# TEC_power1.net
KiCad netlist of a schematic drawn in Altium Designer
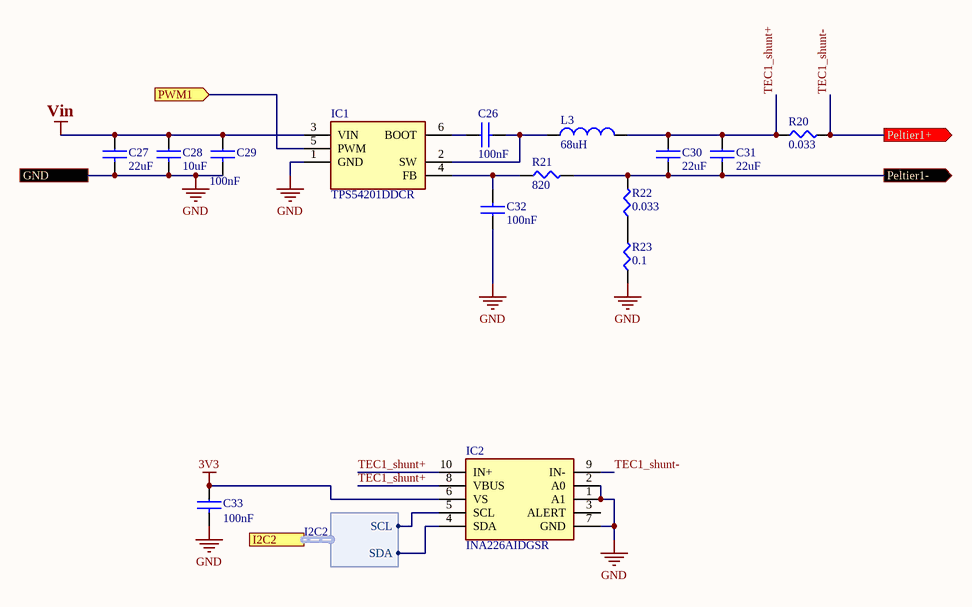
[diagram p0: TEC power1.SchDoc]

(export (version "E")
  (design (tool "Eeschema 10.0.6"))
  (components
    (comp (ref "C26")
      (value "100nF")
      (footprint "CAPC160X80X90L35N")
      (fields (field (name "LCSC PART #") "C14663") (field (name "PART NUMBER") "CC0603KRX7R9BB104"))
      (libsource (lib "Miscellaneous") (part "capacitor"))
    )
    (comp (ref "C27")
      (value "22uF")
      (footprint "CAPC200X125X110L50N")
      (fields (field (name "LCSC PART #") "C45783") (field (name "PART NUMBER") "CL21A226MAQNNNE"))
      (libsource (lib "Miscellaneous") (part "capacitor"))
    )
    (comp (ref "C28")
      (value "10uF")
      (footprint "CAPC200X125X110L50N")
      (fields (field (name "LCSC PART #") "C15850") (field (name "PART NUMBER") "CL21A106KAYNNNE"))
      (libsource (lib "Miscellaneous") (part "capacitor"))
    )
    (comp (ref "C29")
      (value "100nF")
      (footprint "CAPC160X80X90L35N")
      (fields (field (name "LCSC PART #") "C14663") (field (name "PART NUMBER") "CC0603KRX7R9BB104"))
      (libsource (lib "Miscellaneous") (part "capacitor"))
    )
    (comp (ref "C30")
      (value "22uF")
      (footprint "CAPC200X125X110L50N")
      (fields (field (name "LCSC PART #") "C45783") (field (name "PART NUMBER") "CL21A226MAQNNNE"))
      (libsource (lib "Miscellaneous") (part "capacitor"))
    )
    (comp (ref "C31")
      (value "22uF")
      (footprint "CAPC200X125X110L50N")
      (fields (field (name "LCSC PART #") "C45783") (field (name "PART NUMBER") "CL21A226MAQNNNE"))
      (libsource (lib "Miscellaneous") (part "capacitor"))
    )
    (comp (ref "C32")
      (value "100nF")
      (footprint "CAPC160X80X90L35N")
      (fields (field (name "LCSC PART #") "C14663") (field (name "PART NUMBER") "CC0603KRX7R9BB104"))
      (libsource (lib "Miscellaneous") (part "capacitor"))
    )
    (comp (ref "C33")
      (value "100nF")
      (footprint "CAPC160X80X90L35N")
      (fields (field (name "LCSC PART #") "C14663") (field (name "PART NUMBER") "CC0603KRX7R9BB104"))
      (libsource (lib "Miscellaneous") (part "capacitor"))
    )
    (comp (ref "IC1")
      (value "TPS54201DDCR")
      (footprint "SOT95P280X110-6N")
      (description "Integrated Circuit")
      (fields (field (name "MOUSER2 PART NUMBER") "595-TPS54201DDCR") (field (name "PART NUMBER") "TPS54201"))
      (libsource (lib "Miscellaneous") (part "TPS54201DDCR_1"))
    )
    (comp (ref "IC2")
      (value "INA226AIDGSR")
      (footprint "SOP10P50_300X490X110L55X22N")
      (description "Integrated Circuit")
      (fields (field (name "MOUSER2 PART NUMBER") "595-INA226AIDGSR") (field (name "LCSC PART #") "C49851"))
      (libsource (lib "Miscellaneous") (part "INA226AIDGSR"))
    )
    (comp (ref "L3")
      (value "68uH")
      (footprint "INDM1250X1250X800L290X540N")
      (description "Inductor")
      (fields (field (name "LCSC PART #") "C169377") (field (name "PART NUMBER") "SWRB1207S-680MT"))
      (libsource (lib "Miscellaneous") (part "Inductor"))
    )
    (comp (ref "R20")
      (value "0.033")
      (footprint "RESC200X125X70L40N")
      (fields (field (name "LCSC PART #") "C127689"))
      (libsource (lib "Miscellaneous") (part "Resistor"))
    )
    (comp (ref "R21")
      (value "820")
      (footprint "RESC160X80X90L30N")
      (fields (field (name "PART NUMBER") "0603WAF8200T5E") (field (name "LCSC PART #") "C23253"))
      (libsource (lib "Miscellaneous") (part "Resistor"))
    )
    (comp (ref "R22")
      (value "0.033")
      (footprint "RESC200X125X70L40N")
      (fields (field (name "PART NUMBER") "0805W8F330MT5E") (field (name "LCSC PART #") "C127689"))
      (libsource (lib "Miscellaneous") (part "Resistor"))
    )
    (comp (ref "R23")
      (value "0.1")
      (footprint "RESC310X152X65L45N")
      (fields (field (name "PART NUMBER") "1206W4F100LT5E") (field (name "LCSC PART #") "C25334"))
      (libsource (lib "Miscellaneous") (part "Resistor"))
    )
  )
  (nets
    (net (code "2") (name "/PWM1") (class "Default")
      (node (ref "IC1") (pin "5") (pinfunction "PWM_5") (pintype "passive"))
    )
    (net (code "3") (name "/Peltier1-") (class "Default")
      (node (ref "C30") (pin "2") (pinfunction "2_2") (pintype "passive"))
      (node (ref "C31") (pin "2") (pinfunction "2_2") (pintype "passive"))
      (node (ref "R21") (pin "2") (pinfunction "2_2") (pintype "passive"))
      (node (ref "R22") (pin "2") (pinfunction "2_2") (pintype "passive"))
    )
    (net (code "4") (name "/SCL") (class "Default")
      (node (ref "IC2") (pin "5") (pinfunction "SCL_5") (pintype "passive"))
    )
    (net (code "5") (name "/SDA") (class "Default")
      (node (ref "IC2") (pin "4") (pinfunction "SDA_4") (pintype "passive"))
    )
    (net (code "6") (name "/TEC1_shunt+") (class "Default")
      (node (ref "C30") (pin "1") (pinfunction "1_1") (pintype "passive"))
      (node (ref "C31") (pin "1") (pinfunction "1_1") (pintype "passive"))
      (node (ref "IC2") (pin "10") (pinfunction "IN+_10") (pintype "passive"))
      (node (ref "IC2") (pin "8") (pinfunction "VBUS_8") (pintype "passive"))
      (node (ref "L3") (pin "2") (pinfunction "2_2") (pintype "passive"))
      (node (ref "R20") (pin "1") (pinfunction "1_1") (pintype "passive"))
    )
    (net (code "7") (name "/TEC1_shunt-") (class "Default")
      (node (ref "IC2") (pin "9") (pinfunction "IN-_9") (pintype "passive"))
      (node (ref "R20") (pin "2") (pinfunction "2_2") (pintype "passive"))
    )
    (net (code "9") (name "3V3") (class "Default")
      (node (ref "C33") (pin "1") (pinfunction "1_1") (pintype "passive"))
      (node (ref "IC2") (pin "6") (pinfunction "VS_6") (pintype "passive"))
    )
    (net (code "10") (name "GND") (class "Default")
      (node (ref "C27") (pin "2") (pinfunction "2_2") (pintype "passive"))
      (node (ref "C28") (pin "2") (pinfunction "2_2") (pintype "passive"))
      (node (ref "C29") (pin "2") (pinfunction "2_2") (pintype "passive"))
      (node (ref "C32") (pin "1") (pinfunction "1_1") (pintype "passive"))
      (node (ref "C33") (pin "2") (pinfunction "2_2") (pintype "passive"))
      (node (ref "IC1") (pin "1") (pinfunction "GND_1") (pintype "passive"))
      (node (ref "IC2") (pin "1") (pinfunction "A1_1") (pintype "passive"))
      (node (ref "IC2") (pin "2") (pinfunction "A0_2") (pintype "passive"))
      (node (ref "IC2") (pin "7") (pinfunction "GND_7") (pintype "passive"))
      (node (ref "R23") (pin "1") (pinfunction "1_1") (pintype "passive"))
    )
    (net (code "11") (name "Net-(IC1-BOOT)") (class "Default")
      (node (ref "C26") (pin "1") (pinfunction "1_1") (pintype "passive"))
      (node (ref "IC1") (pin "6") (pinfunction "BOOT_6") (pintype "passive"))
    )
    (net (code "12") (name "Net-(IC1-FB)") (class "Default")
      (node (ref "C32") (pin "2") (pinfunction "2_2") (pintype "passive"))
      (node (ref "IC1") (pin "4") (pinfunction "FB_4") (pintype "passive"))
      (node (ref "R21") (pin "1") (pinfunction "1_1") (pintype "passive"))
    )
    (net (code "13") (name "Net-(IC1-SW)") (class "Default")
      (node (ref "C26") (pin "2") (pinfunction "2_2") (pintype "passive"))
      (node (ref "IC1") (pin "2") (pinfunction "SW_2") (pintype "passive"))
      (node (ref "L3") (pin "1") (pinfunction "1_1") (pintype "passive"))
    )
    (net (code "14") (name "Net-(R22-Pad1)") (class "Default")
      (node (ref "R22") (pin "1") (pinfunction "1_1") (pintype "passive"))
      (node (ref "R23") (pin "2") (pinfunction "2_2") (pintype "passive"))
    )
    (net (code "15") (name "Vin") (class "Default")
      (node (ref "C27") (pin "1") (pinfunction "1_1") (pintype "passive"))
      (node (ref "C28") (pin "1") (pinfunction "1_1") (pintype "passive"))
      (node (ref "C29") (pin "1") (pinfunction "1_1") (pintype "passive"))
      (node (ref "IC1") (pin "3") (pinfunction "VIN_3") (pintype "passive"))
    )
    (net (code "16") (name "unconnected-(IC2-ALERT-Pad3)") (class "Default")
      (node (ref "IC2") (pin "3") (pinfunction "ALERT_3") (pintype "passive"))
    )
  )
)
